# Sheet2.net
KiCad netlist of a schematic drawn in Altium Designer
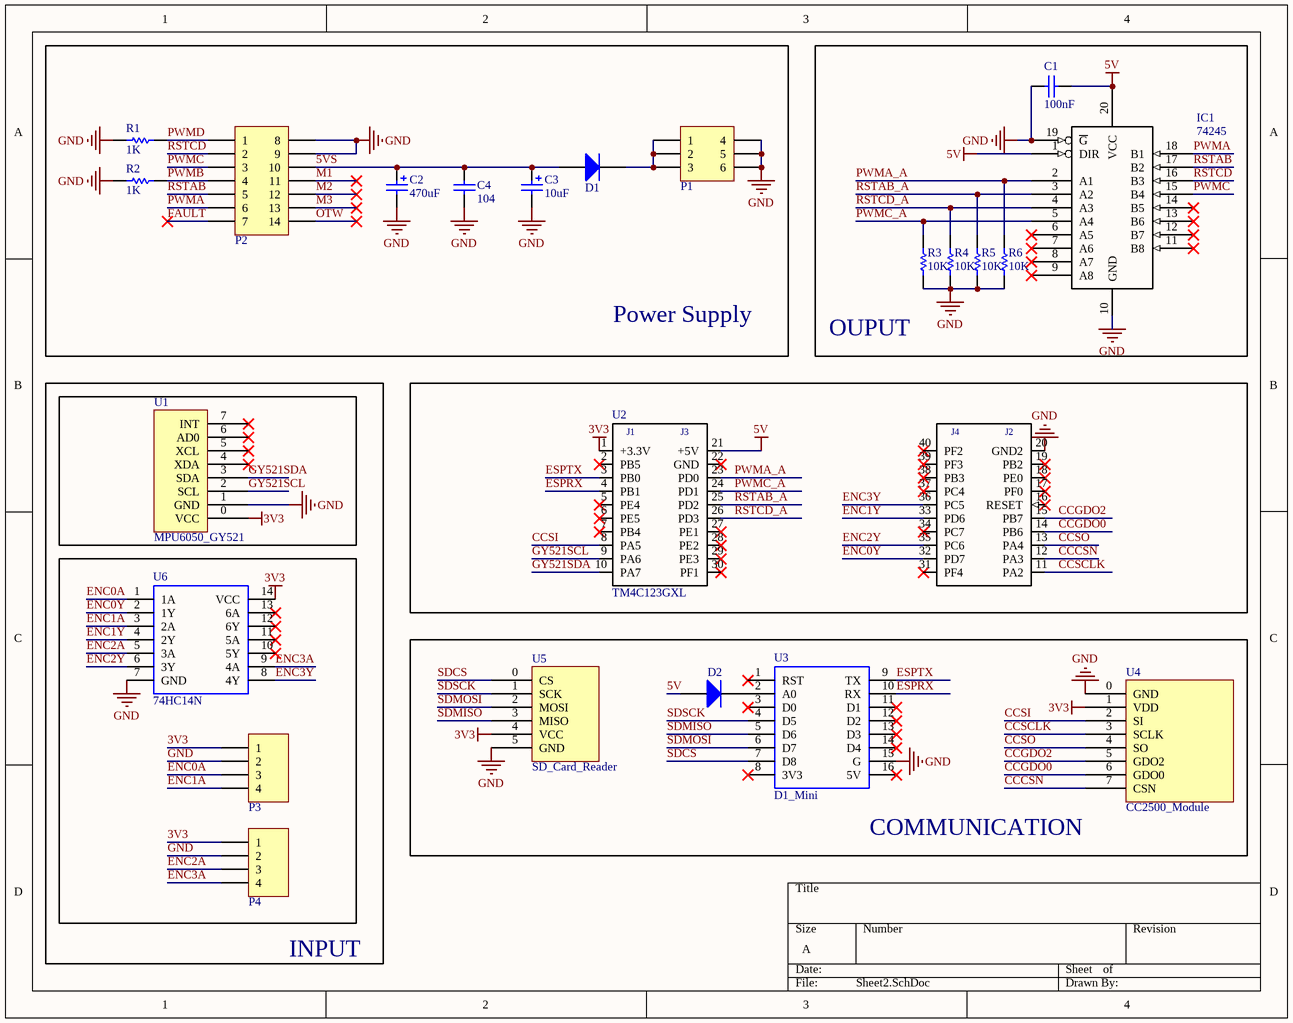
[diagram p0: Sheet2.SchDoc]

(export (version "E")
  (design (tool "Eeschema 10.0.6"))
  (components
    (comp (ref "C1")
      (value "100nF")
      (footprint "CN1")
      (description "Capacitor")
      (fields (field (name "Comment") "Cap Non-Pol"))
      (libsource (lib "PIF_Library") (part "Cap Non-Pol"))
    )
    (comp (ref "C2")
      (value "470uF")
      (footprint "CP1/2")
      (description "Polarized Capacitor (Radial)")
      (fields (field (name "Comment") "Cap Pol"))
      (libsource (lib "PIF_Library") (part "Cap Pol"))
    )
    (comp (ref "C3")
      (value "10uF")
      (footprint "CP1/2")
      (description "Polarized Capacitor (Radial)")
      (fields (field (name "Comment") "Cap Pol"))
      (libsource (lib "PIF_Library") (part "Cap Pol"))
    )
    (comp (ref "C4")
      (value "104")
      (footprint "CN1")
      (description "Capacitor")
      (fields (field (name "Comment") "Cap Non-Pol"))
      (libsource (lib "PIF_Library") (part "Cap Non-Pol"))
    )
    (comp (ref "D1")
      (value "Diode")
      (footprint "D1A")
      (description "Default Diode")
      (libsource (lib "PIF_Library") (part "Diode"))
    )
    (comp (ref "D2")
      (value "Diode")
      (footprint "D1A")
      (description "Default Diode")
      (libsource (lib "PIF_Library") (part "Diode"))
    )
    (comp (ref "IC1")
      (value "74245")
      (footprint "DIP20")
      (description "Octal bus tranceiver; 3-state")
      (fields (field (name "COPYRIGHT BY") "VanDungEvn@gmail.com"))
      (libsource (lib "My Library") (part "74245_1"))
    )
    (comp (ref "P1")
      (value "Header 3X2")
      (footprint "JP3x2")
      (description "Header, 3-Pin, Dual row")
      (fields (field (name "PUBLISHER") "Altium Limited"))
      (libsource (lib "PIF_Library") (part "Header 3X2"))
    )
    (comp (ref "P2")
      (value "Header 7X2")
      (footprint "JP7X2")
      (description "Header, 7-Pin, Dual row")
      (fields (field (name "PUBLISHER") "Altium Limited"))
      (libsource (lib "PIF_Library") (part "Header 7X2"))
    )
    (comp (ref "P3")
      (value "Header 4H")
      (footprint "JP4H")
      (description "Header, 4-Pin, Right Angle")
      (fields (field (name "PUBLISHER") "Altium Limited"))
      (libsource (lib "PIF_Library") (part "Header 4H"))
    )
    (comp (ref "P4")
      (value "Header 4H")
      (footprint "JP4H")
      (description "Header, 4-Pin, Right Angle")
      (fields (field (name "PUBLISHER") "Altium Limited"))
      (libsource (lib "PIF_Library") (part "Header 4H"))
    )
    (comp (ref "R1")
      (value "1K")
      (footprint "RES 1/2W")
      (description "Resistor")
      (fields (field (name "Comment") "RESISTOR"))
      (libsource (lib "PIF_Library") (part "RESISTOR"))
    )
    (comp (ref "R2")
      (value "1K")
      (footprint "RES 1/2W")
      (description "Resistor")
      (fields (field (name "Comment") "RESISTOR"))
      (libsource (lib "PIF_Library") (part "RESISTOR"))
    )
    (comp (ref "R3")
      (value "10K")
      (footprint "RES 1/2W")
      (description "Resistor")
      (fields (field (name "Comment") "RESISTOR"))
      (libsource (lib "PIF_Library") (part "RESISTOR"))
    )
    (comp (ref "R4")
      (value "10K")
      (footprint "RES 1/2W")
      (description "Resistor")
      (fields (field (name "Comment") "RESISTOR"))
      (libsource (lib "PIF_Library") (part "RESISTOR"))
    )
    (comp (ref "R5")
      (value "10K")
      (footprint "RES 1/2W")
      (description "Resistor")
      (fields (field (name "Comment") "RESISTOR"))
      (libsource (lib "PIF_Library") (part "RESISTOR"))
    )
    (comp (ref "R6")
      (value "10K")
      (footprint "RES 1/2W")
      (description "Resistor")
      (fields (field (name "Comment") "RESISTOR"))
      (libsource (lib "PIF_Library") (part "RESISTOR"))
    )
    (comp (ref "U1")
      (value "MPU6050_GY521")
      (footprint "MPU6050_GY521")
      (libsource (lib "AltiumLib") (part "MPU6050_GY521"))
    )
    (comp (ref "U2")
      (value "TM4C123GXL")
      (footprint "EK-TM4C123GXL")
      (libsource (lib "AltiumLib") (part "EK-TM4C123GXL"))
    )
    (comp (ref "U3") (value "D1_Mini") (footprint "D1_Mini") (libsource (lib "AltiumLib") (part "D1_Mini")))
    (comp (ref "U4")
      (value "CC2500_Module")
      (footprint "CC2500_module")
      (libsource (lib "AltiumLib") (part "CC2500_Module"))
    )
    (comp (ref "U5")
      (value "SD_Card_Reader")
      (footprint "SD_Card_Reader")
      (libsource (lib "AltiumLib") (part "SD_Card_Reader"))
    )
    (comp (ref "U6") (value "74HC14N") (footprint "74HC14N") (libsource (lib "AltiumLib") (part "74HC14N")))
  )
  (nets
    (net (code "1") (name "/5VS") (class "Default")
      (node (ref "C2") (pin "1") (pinfunction "1_1") (pintype "passive"))
      (node (ref "C3") (pin "1") (pinfunction "1_1") (pintype "passive"))
      (node (ref "C4") (pin "1") (pinfunction "1_1") (pintype "passive"))
      (node (ref "D1") (pin "1") (pinfunction "A_1") (pintype "passive"))
      (node (ref "P2") (pin "10") (pinfunction "10_10") (pintype "passive"))
    )
    (net (code "2") (name "/CCCSN") (class "Default")
      (node (ref "U2") (pin "12") (pinfunction "PA3_12") (pintype "bidirectional"))
      (node (ref "U4") (pin "7") (pinfunction "CSN_7") (pintype "passive"))
    )
    (net (code "3") (name "/CCGDO0") (class "Default")
      (node (ref "U2") (pin "14") (pinfunction "PB6_14") (pintype "bidirectional"))
      (node (ref "U4") (pin "6") (pinfunction "GDO0_6") (pintype "passive"))
    )
    (net (code "4") (name "/CCGDO2") (class "Default")
      (node (ref "U2") (pin "15") (pinfunction "PB7_15") (pintype "bidirectional"))
      (node (ref "U4") (pin "5") (pinfunction "GDO2_5") (pintype "passive"))
    )
    (net (code "5") (name "/CCSCLK") (class "Default")
      (node (ref "U2") (pin "11") (pinfunction "PA2_11") (pintype "bidirectional"))
      (node (ref "U4") (pin "3") (pinfunction "SCLK_3") (pintype "passive"))
    )
    (net (code "6") (name "/CCSI") (class "Default")
      (node (ref "U2") (pin "8") (pinfunction "PA5_8") (pintype "bidirectional"))
      (node (ref "U4") (pin "2") (pinfunction "SI_2") (pintype "passive"))
    )
    (net (code "7") (name "/CCSO") (class "Default")
      (node (ref "U2") (pin "13") (pinfunction "PA4_13") (pintype "bidirectional"))
      (node (ref "U4") (pin "4") (pinfunction "SO_4") (pintype "passive"))
    )
    (net (code "8") (name "/ENC0A") (class "Default")
      (node (ref "P3") (pin "3") (pinfunction "3_3") (pintype "passive"))
      (node (ref "U6") (pin "1") (pinfunction "1A_1") (pintype "passive"))
    )
    (net (code "9") (name "/ENC0Y") (class "Default")
      (node (ref "U2") (pin "32") (pinfunction "PD7_32") (pintype "bidirectional"))
      (node (ref "U6") (pin "2") (pinfunction "1Y_2") (pintype "passive"))
    )
    (net (code "10") (name "/ENC1A") (class "Default")
      (node (ref "P3") (pin "4") (pinfunction "4_4") (pintype "passive"))
      (node (ref "U6") (pin "3") (pinfunction "2A_3") (pintype "passive"))
    )
    (net (code "11") (name "/ENC1Y") (class "Default")
      (node (ref "U2") (pin "33") (pinfunction "PD6_33") (pintype "bidirectional"))
      (node (ref "U6") (pin "4") (pinfunction "2Y_4") (pintype "passive"))
    )
    (net (code "12") (name "/ENC2A") (class "Default")
      (node (ref "P4") (pin "3") (pinfunction "3_3") (pintype "passive"))
      (node (ref "U6") (pin "5") (pinfunction "3A_5") (pintype "passive"))
    )
    (net (code "13") (name "/ENC2Y") (class "Default")
      (node (ref "U2") (pin "35") (pinfunction "PC6_35") (pintype "bidirectional"))
      (node (ref "U6") (pin "6") (pinfunction "3Y_6") (pintype "passive"))
    )
    (net (code "14") (name "/ENC3A") (class "Default")
      (node (ref "P4") (pin "4") (pinfunction "4_4") (pintype "passive"))
      (node (ref "U6") (pin "9") (pinfunction "4A_9") (pintype "passive"))
    )
    (net (code "15") (name "/ENC3Y") (class "Default")
      (node (ref "U2") (pin "36") (pinfunction "PC5_36") (pintype "bidirectional"))
      (node (ref "U6") (pin "8") (pinfunction "4Y_8") (pintype "passive"))
    )
    (net (code "16") (name "/ESPRX") (class "Default")
      (node (ref "U2") (pin "4") (pinfunction "PB1_4") (pintype "bidirectional"))
      (node (ref "U3") (pin "10") (pinfunction "RX_10") (pintype "passive"))
    )
    (net (code "17") (name "/ESPTX") (class "Default")
      (node (ref "U2") (pin "3") (pinfunction "PB0_3") (pintype "bidirectional"))
      (node (ref "U3") (pin "9") (pinfunction "TX_9") (pintype "passive"))
    )
    (net (code "18") (name "/FAULT") (class "Default")
      (node (ref "P2") (pin "7") (pinfunction "7_7") (pintype "passive+no_connect"))
    )
    (net (code "19") (name "/GY521SCL") (class "Default")
      (node (ref "U1") (pin "2") (pinfunction "SCL_2") (pintype "passive"))
      (node (ref "U2") (pin "9") (pinfunction "PA6_9") (pintype "bidirectional"))
    )
    (net (code "20") (name "/GY521SDA") (class "Default")
      (node (ref "U1") (pin "3") (pinfunction "SDA_3") (pintype "passive"))
      (node (ref "U2") (pin "10") (pinfunction "PA7_10") (pintype "bidirectional"))
    )
    (net (code "21") (name "/M1") (class "Default")
      (node (ref "P2") (pin "11") (pinfunction "11_11") (pintype "passive+no_connect"))
    )
    (net (code "22") (name "/M2") (class "Default")
      (node (ref "P2") (pin "12") (pinfunction "12_12") (pintype "passive+no_connect"))
    )
    (net (code "23") (name "/M3") (class "Default")
      (node (ref "P2") (pin "13") (pinfunction "13_13") (pintype "passive+no_connect"))
    )
    (net (code "24") (name "/OTW") (class "Default")
      (node (ref "P2") (pin "14") (pinfunction "14_14") (pintype "passive+no_connect"))
    )
    (net (code "25") (name "/PWMA") (class "Default")
      (node (ref "IC1") (pin "18") (pinfunction "B1_18") (pintype "input"))
      (node (ref "P2") (pin "6") (pinfunction "6_6") (pintype "passive"))
    )
    (net (code "26") (name "/PWMA_A") (class "Default")
      (node (ref "IC1") (pin "2") (pinfunction "A1_2") (pintype "tri_state"))
      (node (ref "R6") (pin "2") (pinfunction "2_2") (pintype "passive"))
      (node (ref "U2") (pin "23") (pinfunction "PD0_23") (pintype "bidirectional"))
    )
    (net (code "27") (name "/PWMB") (class "Default")
      (node (ref "P2") (pin "4") (pinfunction "4_4") (pintype "passive"))
      (node (ref "R2") (pin "2") (pinfunction "2_2") (pintype "passive"))
    )
    (net (code "28") (name "/PWMC") (class "Default")
      (node (ref "IC1") (pin "15") (pinfunction "B4_15") (pintype "input"))
      (node (ref "P2") (pin "3") (pinfunction "3_3") (pintype "passive"))
    )
    (net (code "29") (name "/PWMC_A") (class "Default")
      (node (ref "IC1") (pin "5") (pinfunction "A4_5") (pintype "tri_state"))
      (node (ref "R3") (pin "2") (pinfunction "2_2") (pintype "passive"))
      (node (ref "U2") (pin "24") (pinfunction "PD1_24") (pintype "bidirectional"))
    )
    (net (code "30") (name "/PWMD") (class "Default")
      (node (ref "P2") (pin "1") (pinfunction "1_1") (pintype "passive"))
      (node (ref "R1") (pin "2") (pinfunction "2_2") (pintype "passive"))
    )
    (net (code "31") (name "/RSTAB") (class "Default")
      (node (ref "IC1") (pin "17") (pinfunction "B2_17") (pintype "input"))
      (node (ref "P2") (pin "5") (pinfunction "5_5") (pintype "passive"))
    )
    (net (code "32") (name "/RSTAB_A") (class "Default")
      (node (ref "IC1") (pin "3") (pinfunction "A2_3") (pintype "tri_state"))
      (node (ref "R5") (pin "2") (pinfunction "2_2") (pintype "passive"))
      (node (ref "U2") (pin "25") (pinfunction "PD2_25") (pintype "bidirectional"))
    )
    (net (code "33") (name "/RSTCD") (class "Default")
      (node (ref "IC1") (pin "16") (pinfunction "B3_16") (pintype "input"))
      (node (ref "P2") (pin "2") (pinfunction "2_2") (pintype "passive"))
    )
    (net (code "34") (name "/RSTCD_A") (class "Default")
      (node (ref "IC1") (pin "4") (pinfunction "A3_4") (pintype "tri_state"))
      (node (ref "R4") (pin "2") (pinfunction "2_2") (pintype "passive"))
      (node (ref "U2") (pin "26") (pinfunction "PD3_26") (pintype "bidirectional"))
    )
    (net (code "35") (name "/SDCS") (class "Default")
      (node (ref "U3") (pin "7") (pinfunction "D8_7") (pintype "passive"))
      (node (ref "U5") (pin "0") (pinfunction "CS_0") (pintype "passive"))
    )
    (net (code "36") (name "/SDMISO") (class "Default")
      (node (ref "U3") (pin "5") (pinfunction "D6_5") (pintype "passive"))
      (node (ref "U5") (pin "3") (pinfunction "MISO_3") (pintype "passive"))
    )
    (net (code "37") (name "/SDMOSI") (class "Default")
      (node (ref "U3") (pin "6") (pinfunction "D7_6") (pintype "passive"))
      (node (ref "U5") (pin "2") (pinfunction "MOSI_2") (pintype "passive"))
    )
    (net (code "38") (name "/SDSCK") (class "Default")
      (node (ref "U3") (pin "4") (pinfunction "D5_4") (pintype "passive"))
      (node (ref "U5") (pin "1") (pinfunction "SCK_1") (pintype "passive"))
    )
    (net (code "39") (name "3V3") (class "Default")
      (node (ref "P3") (pin "1") (pinfunction "1_1") (pintype "passive"))
      (node (ref "P4") (pin "1") (pinfunction "1_1") (pintype "passive"))
      (node (ref "U1") (pin "0") (pinfunction "VCC_0") (pintype "power_in"))
      (node (ref "U2") (pin "1") (pinfunction "+3.3V_1") (pintype "power_in"))
      (node (ref "U4") (pin "1") (pinfunction "VDD_1") (pintype "passive"))
      (node (ref "U5") (pin "4") (pinfunction "VCC_4") (pintype "power_in"))
      (node (ref "U6") (pin "14") (pinfunction "VCC_14") (pintype "passive"))
    )
    (net (code "40") (name "5V") (class "Default")
      (node (ref "C1") (pin "2") (pinfunction "2_2") (pintype "passive"))
      (node (ref "D2") (pin "1") (pinfunction "A_1") (pintype "passive"))
      (node (ref "IC1") (pin "1") (pinfunction "DIR_1") (pintype "input"))
      (node (ref "IC1") (pin "20") (pinfunction "VCC_20") (pintype "power_in"))
      (node (ref "U2") (pin "21") (pinfunction "+5V_21") (pintype "power_in"))
    )
    (net (code "41") (name "GND") (class "Default")
      (node (ref "C1") (pin "1") (pinfunction "1_1") (pintype "passive"))
      (node (ref "C2") (pin "2") (pinfunction "2_2") (pintype "passive"))
      (node (ref "C3") (pin "2") (pinfunction "2_2") (pintype "passive"))
      (node (ref "C4") (pin "2") (pinfunction "2_2") (pintype "passive"))
      (node (ref "IC1") (pin "10") (pinfunction "GND_10") (pintype "power_in"))
      (node (ref "IC1") (pin "19") (pinfunction "~{G}_19") (pintype "input"))
      (node (ref "P1") (pin "4") (pinfunction "4_4") (pintype "passive"))
      (node (ref "P1") (pin "5") (pinfunction "5_5") (pintype "passive"))
      (node (ref "P1") (pin "6") (pinfunction "6_6") (pintype "passive"))
      (node (ref "P2") (pin "8") (pinfunction "8_8") (pintype "passive"))
      (node (ref "P2") (pin "9") (pinfunction "9_9") (pintype "passive"))
      (node (ref "P3") (pin "2") (pinfunction "2_2") (pintype "passive"))
      (node (ref "P4") (pin "2") (pinfunction "2_2") (pintype "passive"))
      (node (ref "R1") (pin "1") (pinfunction "1_1") (pintype "passive"))
      (node (ref "R2") (pin "1") (pinfunction "1_1") (pintype "passive"))
      (node (ref "R3") (pin "1") (pinfunction "1_1") (pintype "passive"))
      (node (ref "R4") (pin "1") (pinfunction "1_1") (pintype "passive"))
      (node (ref "R5") (pin "1") (pinfunction "1_1") (pintype "passive"))
      (node (ref "R6") (pin "1") (pinfunction "1_1") (pintype "passive"))
      (node (ref "U1") (pin "1") (pinfunction "GND_1") (pintype "power_in"))
      (node (ref "U2") (pin "20") (pinfunction "GND2_20") (pintype "power_in"))
      (node (ref "U3") (pin "15") (pinfunction "G_15") (pintype "passive"))
      (node (ref "U4") (pin "0") (pinfunction "GND_0") (pintype "power_in"))
      (node (ref "U5") (pin "5") (pinfunction "GND_5") (pintype "power_in"))
      (node (ref "U6") (pin "7") (pinfunction "GND_7") (pintype "passive"))
    )
    (net (code "42") (name "Net-(D1-K)") (class "Default")
      (node (ref "D1") (pin "2") (pinfunction "K_2") (pintype "passive"))
      (node (ref "P1") (pin "1") (pinfunction "1_1") (pintype "passive"))
      (node (ref "P1") (pin "2") (pinfunction "2_2") (pintype "passive"))
      (node (ref "P1") (pin "3") (pinfunction "3_3") (pintype "passive"))
    )
    (net (code "43") (name "Net-(D2-K)") (class "Default")
      (node (ref "D2") (pin "2") (pinfunction "K_2") (pintype "passive"))
      (node (ref "U3") (pin "2") (pinfunction "A0_2") (pintype "passive"))
    )
    (net (code "44") (name "unconnected-(IC1-A5-Pad6)") (class "Default")
      (node (ref "IC1") (pin "6") (pinfunction "A5_6") (pintype "tri_state+no_connect"))
    )
    (net (code "45") (name "unconnected-(IC1-A6-Pad7)") (class "Default")
      (node (ref "IC1") (pin "7") (pinfunction "A6_7") (pintype "tri_state+no_connect"))
    )
    (net (code "46") (name "unconnected-(IC1-A7-Pad8)") (class "Default")
      (node (ref "IC1") (pin "8") (pinfunction "A7_8") (pintype "tri_state+no_connect"))
    )
    (net (code "47") (name "unconnected-(IC1-A8-Pad9)") (class "Default")
      (node (ref "IC1") (pin "9") (pinfunction "A8_9") (pintype "tri_state+no_connect"))
    )
    (net (code "48") (name "unconnected-(IC1-B5-Pad14)") (class "Default")
      (node (ref "IC1") (pin "14") (pinfunction "B5_14") (pintype "input+no_connect"))
    )
    (net (code "49") (name "unconnected-(IC1-B6-Pad13)") (class "Default")
      (node (ref "IC1") (pin "13") (pinfunction "B6_13") (pintype "input+no_connect"))
    )
    (net (code "50") (name "unconnected-(IC1-B7-Pad12)") (class "Default")
      (node (ref "IC1") (pin "12") (pinfunction "B7_12") (pintype "input+no_connect"))
    )
    (net (code "51") (name "unconnected-(IC1-B8-Pad11)") (class "Default")
      (node (ref "IC1") (pin "11") (pinfunction "B8_11") (pintype "input+no_connect"))
    )
    (net (code "52") (name "unconnected-(U1-AD0-Pad6)") (class "Default")
      (node (ref "U1") (pin "6") (pinfunction "AD0_6") (pintype "passive+no_connect"))
    )
    (net (code "53") (name "unconnected-(U1-INT-Pad7)") (class "Default")
      (node (ref "U1") (pin "7") (pinfunction "INT_7") (pintype "passive+no_connect"))
    )
    (net (code "54") (name "unconnected-(U1-XCL-Pad5)") (class "Default")
      (node (ref "U1") (pin "5") (pinfunction "XCL_5") (pintype "passive+no_connect"))
    )
    (net (code "55") (name "unconnected-(U1-XDA-Pad4)") (class "Default")
      (node (ref "U1") (pin "4") (pinfunction "XDA_4") (pintype "passive+no_connect"))
    )
    (net (code "56") (name "unconnected-(U2-GND-Pad22)") (class "Default")
      (node (ref "U2") (pin "22") (pinfunction "GND_22") (pintype "power_in+no_connect"))
    )
    (net (code "57") (name "unconnected-(U2-PB2-Pad19)") (class "Default")
      (node (ref "U2") (pin "19") (pinfunction "PB2_19") (pintype "bidirectional+no_connect"))
    )
    (net (code "58") (name "unconnected-(U2-PB3-Pad38)") (class "Default")
      (node (ref "U2") (pin "38") (pinfunction "PB3_38") (pintype "bidirectional+no_connect"))
    )
    (net (code "59") (name "unconnected-(U2-PB4-Pad7)") (class "Default")
      (node (ref "U2") (pin "7") (pinfunction "PB4_7") (pintype "bidirectional+no_connect"))
    )
    (net (code "60") (name "unconnected-(U2-PB5-Pad2)") (class "Default")
      (node (ref "U2") (pin "2") (pinfunction "PB5_2") (pintype "bidirectional+no_connect"))
    )
    (net (code "61") (name "unconnected-(U2-PC4-Pad37)") (class "Default")
      (node (ref "U2") (pin "37") (pinfunction "PC4_37") (pintype "bidirectional+no_connect"))
    )
    (net (code "62") (name "unconnected-(U2-PC7-Pad34)") (class "Default")
      (node (ref "U2") (pin "34") (pinfunction "PC7_34") (pintype "bidirectional+no_connect"))
    )
    (net (code "63") (name "unconnected-(U2-PE0-Pad18)") (class "Default")
      (node (ref "U2") (pin "18") (pinfunction "PE0_18") (pintype "bidirectional+no_connect"))
    )
    (net (code "64") (name "unconnected-(U2-PE1-Pad27)") (class "Default")
      (node (ref "U2") (pin "27") (pinfunction "PE1_27") (pintype "bidirectional+no_connect"))
    )
    (net (code "65") (name "unconnected-(U2-PE2-Pad28)") (class "Default")
      (node (ref "U2") (pin "28") (pinfunction "PE2_28") (pintype "bidirectional+no_connect"))
    )
    (net (code "66") (name "unconnected-(U2-PE3-Pad29)") (class "Default")
      (node (ref "U2") (pin "29") (pinfunction "PE3_29") (pintype "bidirectional+no_connect"))
    )
    (net (code "67") (name "unconnected-(U2-PE4-Pad5)") (class "Default")
      (node (ref "U2") (pin "5") (pinfunction "PE4_5") (pintype "bidirectional+no_connect"))
    )
    (net (code "68") (name "unconnected-(U2-PE5-Pad6)") (class "Default")
      (node (ref "U2") (pin "6") (pinfunction "PE5_6") (pintype "bidirectional+no_connect"))
    )
    (net (code "69") (name "unconnected-(U2-PF0-Pad17)") (class "Default")
      (node (ref "U2") (pin "17") (pinfunction "PF0_17") (pintype "bidirectional+no_connect"))
    )
    (net (code "70") (name "unconnected-(U2-PF1-Pad30)") (class "Default")
      (node (ref "U2") (pin "30") (pinfunction "PF1_30") (pintype "bidirectional+no_connect"))
    )
    (net (code "71") (name "unconnected-(U2-PF2-Pad40)") (class "Default")
      (node (ref "U2") (pin "40") (pinfunction "PF2_40") (pintype "bidirectional+no_connect"))
    )
    (net (code "72") (name "unconnected-(U2-PF3-Pad39)") (class "Default")
      (node (ref "U2") (pin "39") (pinfunction "PF3_39") (pintype "bidirectional+no_connect"))
    )
    (net (code "73") (name "unconnected-(U2-PF4-Pad31)") (class "Default")
      (node (ref "U2") (pin "31") (pinfunction "PF4_31") (pintype "bidirectional+no_connect"))
    )
    (net (code "74") (name "unconnected-(U2-RESET-Pad16)") (class "Default")
      (node (ref "U2") (pin "16") (pinfunction "RESET_16") (pintype "input+no_connect"))
    )
    (net (code "75") (name "unconnected-(U3-3V3-Pad8)") (class "Default")
      (node (ref "U3") (pin "8") (pinfunction "3V3_8") (pintype "passive+no_connect"))
    )
    (net (code "76") (name "unconnected-(U3-5V-Pad16)") (class "Default")
      (node (ref "U3") (pin "16") (pinfunction "5V_16") (pintype "passive+no_connect"))
    )
    (net (code "77") (name "unconnected-(U3-D0-Pad3)") (class "Default")
      (node (ref "U3") (pin "3") (pinfunction "D0_3") (pintype "passive+no_connect"))
    )
    (net (code "78") (name "unconnected-(U3-D1-Pad11)") (class "Default")
      (node (ref "U3") (pin "11") (pinfunction "D1_11") (pintype "passive+no_connect"))
    )
    (net (code "79") (name "unconnected-(U3-D2-Pad12)") (class "Default")
      (node (ref "U3") (pin "12") (pinfunction "D2_12") (pintype "passive+no_connect"))
    )
    (net (code "80") (name "unconnected-(U3-D3-Pad13)") (class "Default")
      (node (ref "U3") (pin "13") (pinfunction "D3_13") (pintype "passive+no_connect"))
    )
    (net (code "81") (name "unconnected-(U3-D4-Pad14)") (class "Default")
      (node (ref "U3") (pin "14") (pinfunction "D4_14") (pintype "passive+no_connect"))
    )
    (net (code "82") (name "unconnected-(U3-RST-Pad1)") (class "Default")
      (node (ref "U3") (pin "1") (pinfunction "RST_1") (pintype "passive+no_connect"))
    )
    (net (code "83") (name "unconnected-(U6-5A-Pad11)") (class "Default")
      (node (ref "U6") (pin "11") (pinfunction "5A_11") (pintype "passive+no_connect"))
    )
    (net (code "84") (name "unconnected-(U6-5Y-Pad10)") (class "Default")
      (node (ref "U6") (pin "10") (pinfunction "5Y_10") (pintype "passive+no_connect"))
    )
    (net (code "85") (name "unconnected-(U6-6A-Pad13)") (class "Default")
      (node (ref "U6") (pin "13") (pinfunction "6A_13") (pintype "passive+no_connect"))
    )
    (net (code "86") (name "unconnected-(U6-6Y-Pad12)") (class "Default")
      (node (ref "U6") (pin "12") (pinfunction "6Y_12") (pintype "passive+no_connect"))
    )
  )
)
